# I2C_Interfave.net
KiCad netlist of a schematic drawn in Altium Designer
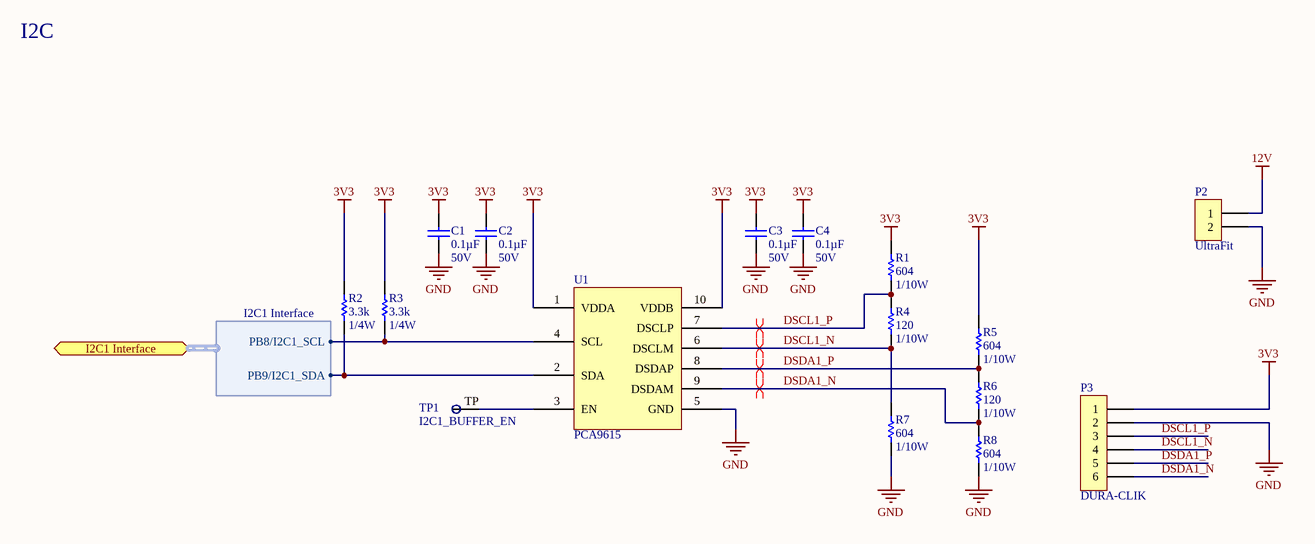
[diagram p0: I2C_Interfave.SchDoc]

(export (version "E")
  (design (tool "Eeschema 10.0.6"))
  (components
    (comp (ref "C1")
      (value "CAP CER 0.1UF 50V 10% X7R 0603")
      (footprint "CAP, 0603")
      (description "0.10µF ±10% 50V Ceramic Capacitor X7R 0603 (1608 Metric)")
      (fields
        (field (name "TOLERANCE") "±10%")
        (field (name "CAPACITANCE") "0.1µF")
        (field (name "VOLTAGE") "50V")
      )
      (libsource (lib "Schematic Diagrams") (part "CAP CER 0.1UF 50V 10% X7R 0603"))
    )
    (comp (ref "C2")
      (value "CAP CER 0.1UF 50V 10% X7R 0603")
      (footprint "CAP, 0603")
      (description "0.10µF ±10% 50V Ceramic Capacitor X7R 0603 (1608 Metric)")
      (fields
        (field (name "TOLERANCE") "±10%")
        (field (name "CAPACITANCE") "0.1µF")
        (field (name "VOLTAGE") "50V")
      )
      (libsource (lib "Schematic Diagrams") (part "CAP CER 0.1UF 50V 10% X7R 0603"))
    )
    (comp (ref "C3")
      (value "CAP CER 0.1UF 50V 10% X7R 0603")
      (footprint "CAP, 0603")
      (description "0.10µF ±10% 50V Ceramic Capacitor X7R 0603 (1608 Metric)")
      (fields
        (field (name "TOLERANCE") "±10%")
        (field (name "CAPACITANCE") "0.1µF")
        (field (name "VOLTAGE") "50V")
      )
      (libsource (lib "Schematic Diagrams") (part "CAP CER 0.1UF 50V 10% X7R 0603"))
    )
    (comp (ref "C4")
      (value "CAP CER 0.1UF 50V 10% X7R 0603")
      (footprint "CAP, 0603")
      (description "0.10µF ±10% 50V Ceramic Capacitor X7R 0603 (1608 Metric)")
      (fields
        (field (name "TOLERANCE") "±10%")
        (field (name "CAPACITANCE") "0.1µF")
        (field (name "VOLTAGE") "50V")
      )
      (libsource (lib "Schematic Diagrams") (part "CAP CER 0.1UF 50V 10% X7R 0603"))
    )
    (comp (ref "P2")
      (value "CONN 2POS ULTRA-FIT 0.138\"")
      (footprint "CONN, 2POS ULTRA-FIT")
      (description "2 Positions Header, Shrouded Connector 0.138\" (3.50mm) Through Hole Gold")
      (fields (field (name "VOLTAGE") "400V") (field (name "SERIES") "UltraFit"))
      (libsource (lib "Schematic Diagrams") (part "CONN 2POS ULTRA-FIT 0.138{dblquote}"))
    )
    (comp (ref "P3")
      (value "DURA-CLIK")
      (footprint "CONN, 6POS DURA-CLIK VERT")
      (description "6 Positions Header, Shrouded Connector 0.079\" (2.00mm) Surface Mount, Vertical Tin")
      (fields (field (name "MANUFACTURER") "Molex") (field (name "MANUFACTURER PART NUMBER") "5600200820"))
      (libsource (lib "Schematic Diagrams") (part "CONN 6POS DURA-CLIK 0.079{dblquote}"))
    )
    (comp (ref "R1")
      (value "RES 604 OHM 1% 1/10W 0603")
      (footprint "RES, 0603")
      (description "RES SMD 604 OHM 1% 1/10W 0603")
      (fields
        (field (name "TOLERANCE") "±1%")
        (field (name "RESISTANCE") "604")
        (field (name "POWER") "1/10W")
      )
      (libsource (lib "Schematic Diagrams") (part "RES 604 OHM 1% 1/10W 0603"))
    )
    (comp (ref "R2")
      (value "RES 3.3K OHM 1% 1/4W 0603")
      (footprint "RES, 0603")
      (fields
        (field (name "TOLERANCE") "±1%")
        (field (name "RESISTANCE") "3.3k")
        (field (name "POWER") "1/4W")
      )
      (libsource (lib "Schematic Diagrams") (part "RES 3.3K OHM 1% 1/4W 0603"))
    )
    (comp (ref "R3")
      (value "RES 3.3K OHM 1% 1/4W 0603")
      (footprint "RES, 0603")
      (fields
        (field (name "TOLERANCE") "±1%")
        (field (name "RESISTANCE") "3.3k")
        (field (name "POWER") "1/4W")
      )
      (libsource (lib "Schematic Diagrams") (part "RES 3.3K OHM 1% 1/4W 0603"))
    )
    (comp (ref "R4")
      (value "RES 120 OHM 1% 1/10W 0603")
      (footprint "RES, 0603")
      (description "RES SMD 120 OHM 1% 1/10W 0603")
      (fields
        (field (name "TOLERANCE") "±1%")
        (field (name "RESISTANCE") "120")
        (field (name "POWER") "1/10W")
      )
      (libsource (lib "Schematic Diagrams") (part "RES 120 OHM 1% 1/10W 0603"))
    )
    (comp (ref "R5")
      (value "RES 604 OHM 1% 1/10W 0603")
      (footprint "RES, 0603")
      (description "RES SMD 604 OHM 1% 1/10W 0603")
      (fields
        (field (name "TOLERANCE") "±1%")
        (field (name "RESISTANCE") "604")
        (field (name "POWER") "1/10W")
      )
      (libsource (lib "Schematic Diagrams") (part "RES 604 OHM 1% 1/10W 0603"))
    )
    (comp (ref "R6")
      (value "RES 120 OHM 1% 1/10W 0603")
      (footprint "RES, 0603")
      (description "RES SMD 120 OHM 1% 1/10W 0603")
      (fields
        (field (name "TOLERANCE") "±1%")
        (field (name "RESISTANCE") "120")
        (field (name "POWER") "1/10W")
      )
      (libsource (lib "Schematic Diagrams") (part "RES 120 OHM 1% 1/10W 0603"))
    )
    (comp (ref "R7")
      (value "RES 604 OHM 1% 1/10W 0603")
      (footprint "RES, 0603")
      (description "RES SMD 604 OHM 1% 1/10W 0603")
      (fields
        (field (name "TOLERANCE") "±1%")
        (field (name "RESISTANCE") "604")
        (field (name "POWER") "1/10W")
      )
      (libsource (lib "Schematic Diagrams") (part "RES 604 OHM 1% 1/10W 0603"))
    )
    (comp (ref "R8")
      (value "RES 604 OHM 1% 1/10W 0603")
      (footprint "RES, 0603")
      (description "RES SMD 604 OHM 1% 1/10W 0603")
      (fields
        (field (name "TOLERANCE") "±1%")
        (field (name "RESISTANCE") "604")
        (field (name "POWER") "1/10W")
      )
      (libsource (lib "Schematic Diagrams") (part "RES 604 OHM 1% 1/10W 0603"))
    )
    (comp (ref "TP1")
      (value "I2C1_BUFFER_EN")
      (footprint "Test Point")
      (libsource (lib "Schematic Diagrams") (part "Test Point"))
    )
    (comp (ref "U1")
      (value "IC DIFFERENTIAL I2C BUFFER PCA9615")
      (footprint "TSSOP50P490X110-10N")
      (description "Buffer, ReDriver 2 Channel 400kHz 10-TSSOP")
      (fields
        (field (name "MANUFACTURER") "NXP USA Inc.")
        (field (name "MANUFACTURER PART NUMBER") "PCA9615DPJ")
        (field (name "BASE PART NUMBER") "PCA9615")
      )
      (libsource (lib "Schematic Diagrams") (part "IC DIFFERENTIAL I2C BUFFER PCA9615"))
    )
  )
  (nets
    (net (code "3") (name "/DSCL1_N") (class "Default")
      (node (ref "P3") (pin "4") (pinfunction "4_4") (pintype "passive"))
      (node (ref "R4") (pin "2") (pinfunction "2_2") (pintype "passive"))
      (node (ref "R7") (pin "1") (pinfunction "1_1") (pintype "passive"))
      (node (ref "U1") (pin "6") (pinfunction "DSCLM_6") (pintype "passive"))
    )
    (net (code "4") (name "/DSCL1_P") (class "Default")
      (node (ref "P3") (pin "3") (pinfunction "3_3") (pintype "passive"))
      (node (ref "R1") (pin "2") (pinfunction "2_2") (pintype "passive"))
      (node (ref "R4") (pin "1") (pinfunction "1_1") (pintype "passive"))
      (node (ref "U1") (pin "7") (pinfunction "DSCLP_7") (pintype "passive"))
    )
    (net (code "5") (name "/DSDA1_N") (class "Default")
      (node (ref "P3") (pin "6") (pinfunction "6_6") (pintype "passive"))
      (node (ref "R6") (pin "2") (pinfunction "2_2") (pintype "passive"))
      (node (ref "R8") (pin "1") (pinfunction "1_1") (pintype "passive"))
      (node (ref "U1") (pin "9") (pinfunction "DSDAM_9") (pintype "passive"))
    )
    (net (code "6") (name "/DSDA1_P") (class "Default")
      (node (ref "P3") (pin "5") (pinfunction "5_5") (pintype "passive"))
      (node (ref "R5") (pin "2") (pinfunction "2_2") (pintype "passive"))
      (node (ref "R6") (pin "1") (pinfunction "1_1") (pintype "passive"))
      (node (ref "U1") (pin "8") (pinfunction "DSDAP_8") (pintype "passive"))
    )
    (net (code "8") (name "3V3") (class "Default")
      (node (ref "C1") (pin "1") (pinfunction "1_1") (pintype "passive"))
      (node (ref "C2") (pin "1") (pinfunction "1_1") (pintype "passive"))
      (node (ref "C3") (pin "1") (pinfunction "1_1") (pintype "passive"))
      (node (ref "C4") (pin "1") (pinfunction "1_1") (pintype "passive"))
      (node (ref "P3") (pin "1") (pinfunction "1_1") (pintype "passive"))
      (node (ref "R1") (pin "1") (pinfunction "1_1") (pintype "passive"))
      (node (ref "R2") (pin "1") (pinfunction "1_1") (pintype "passive"))
      (node (ref "R3") (pin "1") (pinfunction "1_1") (pintype "passive"))
      (node (ref "R5") (pin "1") (pinfunction "1_1") (pintype "passive"))
      (node (ref "U1") (pin "1") (pinfunction "VDDA_1") (pintype "passive"))
      (node (ref "U1") (pin "10") (pinfunction "VDDB_10") (pintype "passive"))
    )
    (net (code "9") (name "12V") (class "Default")
      (node (ref "P2") (pin "1") (pinfunction "1_1") (pintype "passive"))
    )
    (net (code "10") (name "GND") (class "Default")
      (node (ref "C1") (pin "2") (pinfunction "2_2") (pintype "passive"))
      (node (ref "C2") (pin "2") (pinfunction "2_2") (pintype "passive"))
      (node (ref "C3") (pin "2") (pinfunction "2_2") (pintype "passive"))
      (node (ref "C4") (pin "2") (pinfunction "2_2") (pintype "passive"))
      (node (ref "P2") (pin "2") (pinfunction "2_2") (pintype "passive"))
      (node (ref "P3") (pin "2") (pinfunction "2_2") (pintype "passive"))
      (node (ref "R7") (pin "2") (pinfunction "2_2") (pintype "passive"))
      (node (ref "R8") (pin "2") (pinfunction "2_2") (pintype "passive"))
      (node (ref "U1") (pin "5") (pinfunction "GND_5") (pintype "passive"))
    )
    (net (code "11") (name "Net-(TP1-1)") (class "Default")
      (node (ref "TP1") (pin "TP") (pinfunction "1_TP") (pintype "passive"))
      (node (ref "U1") (pin "3") (pinfunction "EN_3") (pintype "passive"))
    )
    (net (code "12") (name "Net-(U1-SCL)") (class "Default")
      (node (ref "R3") (pin "2") (pinfunction "2_2") (pintype "passive"))
      (node (ref "U1") (pin "4") (pinfunction "SCL_4") (pintype "passive"))
    )
    (net (code "13") (name "Net-(U1-SDA)") (class "Default")
      (node (ref "R2") (pin "2") (pinfunction "2_2") (pintype "passive"))
      (node (ref "U1") (pin "2") (pinfunction "SDA_2") (pintype "passive"))
    )
  )
)
